# DM1098OAKW_QWIIC.net
KiCad netlist of a schematic drawn in Altium Designer
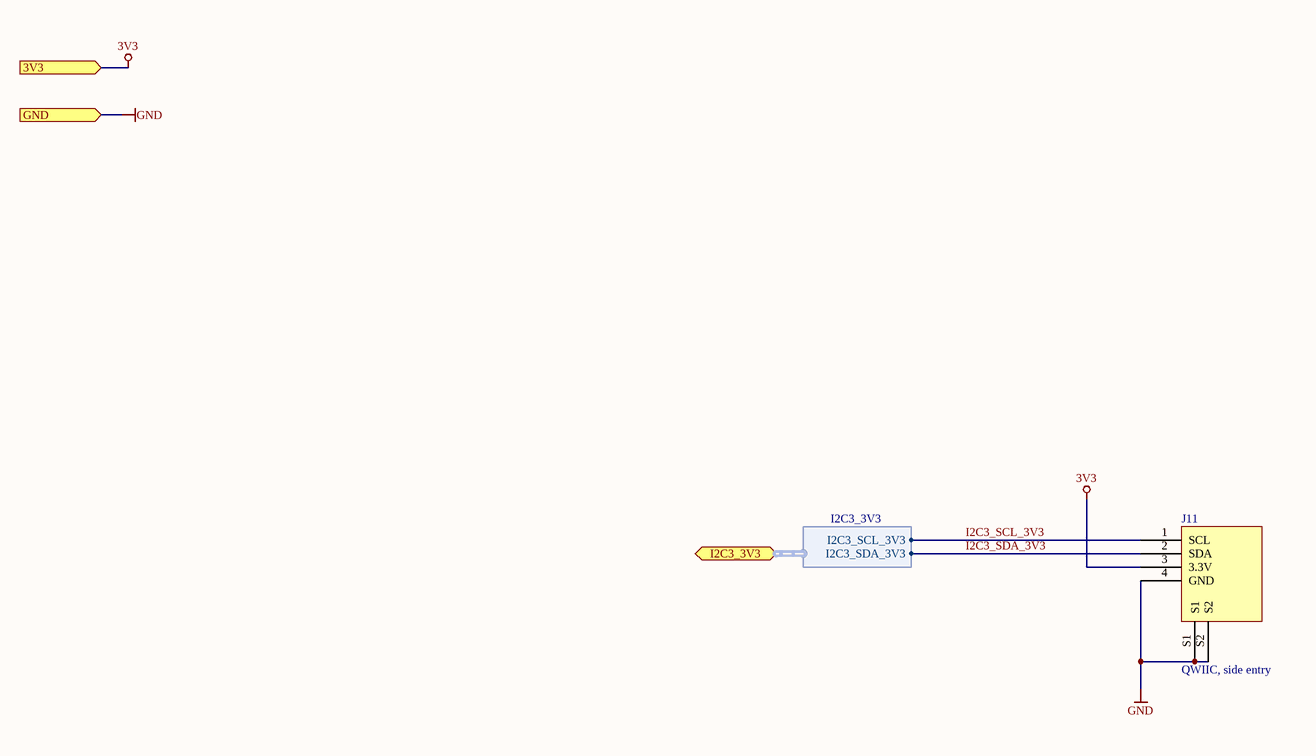
[diagram p0: DM1098OAKW_QWIIC.SchDoc]

(export (version "E")
  (design (tool "Eeschema 10.0.6"))
  (components
    (comp (ref "J11")
      (value "QWIIC, side entry")
      (footprint "BW1092_R0M0E0:SM04B-SRSS-TB(LF)(SN)")
      (description "Connector Header, Side Entry, SR Series, 4 Position, 1.00mm, 50V, Surface Mount, Tin, Natural")
      (libsource (lib "BW1092_R0M0E0") (part "SM04B-SRSS-TB(LF)(SN)"))
    )
  )
  (nets
    (net (code "2") (name "/I2C3_SCL_3V3") (class "Default")
      (node (ref "J11") (pin "1") (pinfunction "SCL_1") (pintype "passive"))
    )
    (net (code "3") (name "/I2C3_SDA_3V3") (class "Default")
      (node (ref "J11") (pin "2") (pinfunction "SDA_2") (pintype "passive"))
    )
    (net (code "5") (name "3V3") (class "Default")
      (node (ref "J11") (pin "3") (pinfunction "3.3V_3") (pintype "passive"))
    )
    (net (code "6") (name "GND") (class "Default")
      (node (ref "J11") (pin "4") (pinfunction "GND_4") (pintype "passive"))
      (node (ref "J11") (pin "S1") (pinfunction "S1_S1") (pintype "passive"))
      (node (ref "J11") (pin "S2") (pinfunction "S2_S2") (pintype "passive"))
    )
  )
)
